# stm32f4discovery-daugherboard-v1-THT.net
KiCad netlist of a schematic drawn in EAGLE
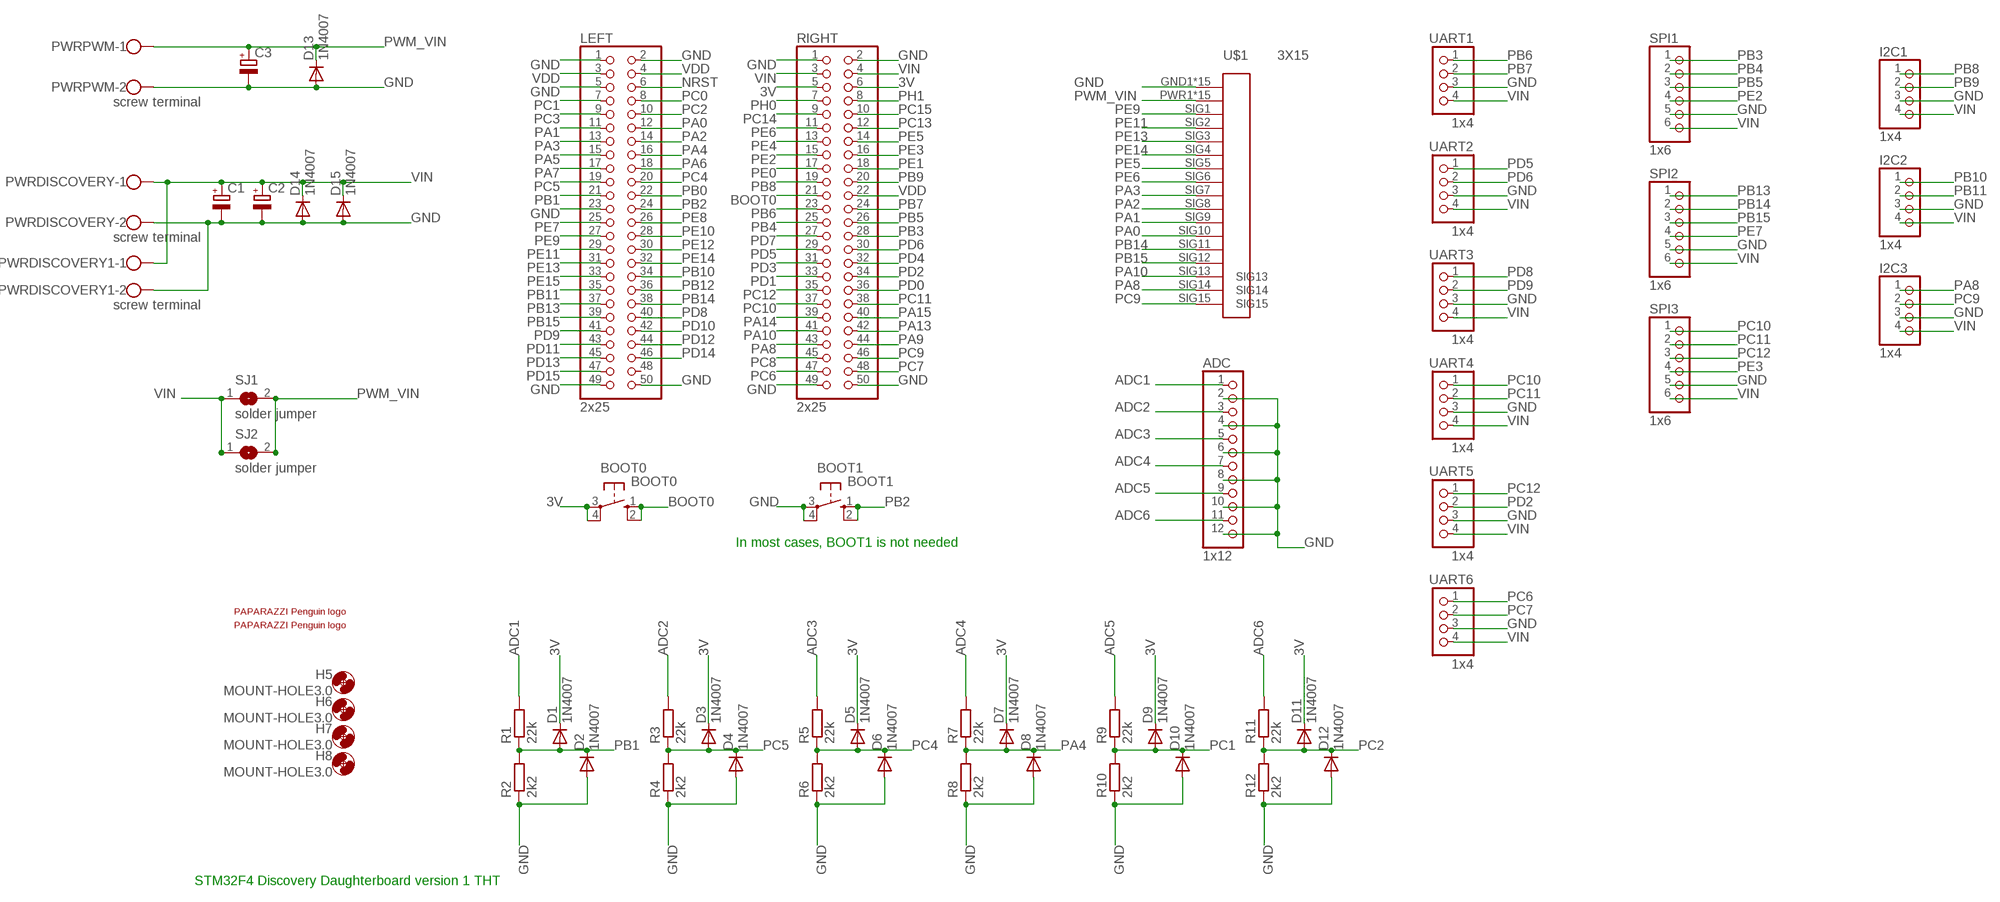
[diagram p0: schematic, sheet 1]

(export (version "E")
  (design (tool "Eeschema 10.0.6"))
  (components
    (comp (ref "ADC")
      (value "1x12")
      (footprint "eagle-import:1X12_90")
      (libsource (lib "eagle-import") (part "PINHD-1X12/90"))
    )
    (comp (ref "BOOT0")
      (value "BOOT0")
      (footprint "eagle-import:B3F-10XX")
      (fields (field (name "MPN") "B3F-1000"))
      (libsource (lib "eagle-import") (part "10-XX"))
    )
    (comp (ref "BOOT1")
      (value "BOOT1")
      (footprint "eagle-import:B3F-10XX")
      (fields (field (name "MPN") "B3F-1000"))
      (libsource (lib "eagle-import") (part "10-XX"))
    )
    (comp (ref "C1")
      (value "CPOL-EUE5-8.5")
      (footprint "eagle-import:E5-8,5")
      (libsource (lib "eagle-import") (part "CPOL-EUE5-8.5"))
    )
    (comp (ref "C2")
      (value "CPOL-EUE5-8.5")
      (footprint "eagle-import:E5-8,5")
      (libsource (lib "eagle-import") (part "CPOL-EUE5-8.5"))
    )
    (comp (ref "C3")
      (value "CPOL-EUE5-8.5")
      (footprint "eagle-import:E5-8,5")
      (libsource (lib "eagle-import") (part "CPOL-EUE5-8.5"))
    )
    (comp (ref "D1")
      (value "1N4007")
      (footprint "eagle-import:DO41-7.6_2")
      (libsource (lib "eagle-import") (part "1N4007"))
    )
    (comp (ref "D2")
      (value "1N4007")
      (footprint "eagle-import:DO41-7.6_2")
      (libsource (lib "eagle-import") (part "1N4007"))
    )
    (comp (ref "D3")
      (value "1N4007")
      (footprint "eagle-import:DO41-7.6_2")
      (libsource (lib "eagle-import") (part "1N4007"))
    )
    (comp (ref "D4")
      (value "1N4007")
      (footprint "eagle-import:DO41-7.6_2")
      (libsource (lib "eagle-import") (part "1N4007"))
    )
    (comp (ref "D5")
      (value "1N4007")
      (footprint "eagle-import:DO41-7.6_2")
      (libsource (lib "eagle-import") (part "1N4007"))
    )
    (comp (ref "D6")
      (value "1N4007")
      (footprint "eagle-import:DO41-7.6_2")
      (libsource (lib "eagle-import") (part "1N4007"))
    )
    (comp (ref "D7")
      (value "1N4007")
      (footprint "eagle-import:DO41-7.6_2")
      (libsource (lib "eagle-import") (part "1N4007"))
    )
    (comp (ref "D8")
      (value "1N4007")
      (footprint "eagle-import:DO41-7.6_2")
      (libsource (lib "eagle-import") (part "1N4007"))
    )
    (comp (ref "D9")
      (value "1N4007")
      (footprint "eagle-import:DO41-7.6_2")
      (libsource (lib "eagle-import") (part "1N4007"))
    )
    (comp (ref "D10")
      (value "1N4007")
      (footprint "eagle-import:DO41-7.6_2")
      (libsource (lib "eagle-import") (part "1N4007"))
    )
    (comp (ref "D11")
      (value "1N4007")
      (footprint "eagle-import:DO41-7.6_2")
      (libsource (lib "eagle-import") (part "1N4007"))
    )
    (comp (ref "D12")
      (value "1N4007")
      (footprint "eagle-import:DO41-7.6_2")
      (libsource (lib "eagle-import") (part "1N4007"))
    )
    (comp (ref "D13")
      (value "1N4007")
      (footprint "eagle-import:DO41-7.6_2")
      (libsource (lib "eagle-import") (part "1N4007"))
    )
    (comp (ref "D14")
      (value "1N4007")
      (footprint "eagle-import:DO41-7.6_2")
      (libsource (lib "eagle-import") (part "1N4007"))
    )
    (comp (ref "D15")
      (value "1N4007")
      (footprint "eagle-import:DO41-7.6_2")
      (libsource (lib "eagle-import") (part "1N4007"))
    )
    (comp (ref "H5")
      (value "MOUNT-HOLE3.0")
      (footprint "eagle-import:3,0")
      (libsource (lib "eagle-import") (part "MOUNT-HOLE3.0"))
    )
    (comp (ref "H6")
      (value "MOUNT-HOLE3.0")
      (footprint "eagle-import:3,0")
      (libsource (lib "eagle-import") (part "MOUNT-HOLE3.0"))
    )
    (comp (ref "H7")
      (value "MOUNT-HOLE3.0")
      (footprint "eagle-import:3,0")
      (libsource (lib "eagle-import") (part "MOUNT-HOLE3.0"))
    )
    (comp (ref "H8")
      (value "MOUNT-HOLE3.0")
      (footprint "eagle-import:3,0")
      (libsource (lib "eagle-import") (part "MOUNT-HOLE3.0"))
    )
    (comp (ref "I2C1")
      (value "1x4")
      (footprint "eagle-import:1X04_90")
      (libsource (lib "eagle-import") (part "PINHD-1X4/90"))
    )
    (comp (ref "I2C2")
      (value "1x4")
      (footprint "eagle-import:1X04_90")
      (libsource (lib "eagle-import") (part "PINHD-1X4/90"))
    )
    (comp (ref "I2C3")
      (value "1x4")
      (footprint "eagle-import:1X04_90")
      (libsource (lib "eagle-import") (part "PINHD-1X4/90"))
    )
    (comp (ref "LEFT")
      (value "2x25")
      (footprint "eagle-import:2X25")
      (libsource (lib "eagle-import") (part "PINHD-2X25"))
    )
    (comp (ref "PWRDISCOVERY")
      (value "screw terminal")
      (footprint "eagle-import:W237-102")
      (fields (field (name "MPN") "237-102"))
      (libsource (lib "eagle-import") (part "W237-102"))
    )
    (comp (ref "PWRDISCOVERY1")
      (value "screw terminal")
      (footprint "eagle-import:W237-102")
      (fields
        (field (name "MPN") "237-102")
        (field (name "MPN_1") "237-102")
        (field (name "OC_FARNELL") "unknown")
        (field (name "OC_NEWARK") "70K9898")
      )
      (libsource (lib "eagle-import") (part "W237-102"))
    )
    (comp (ref "PWRPWM")
      (value "screw terminal")
      (footprint "eagle-import:W237-102")
      (fields (field (name "MPN") "237-102"))
      (libsource (lib "eagle-import") (part "W237-102"))
    )
    (comp (ref "R1")
      (value "22k")
      (footprint "eagle-import:0204_7")
      (libsource (lib "eagle-import") (part "R-EU_0204/7"))
    )
    (comp (ref "R2")
      (value "2k2")
      (footprint "eagle-import:0204_7")
      (libsource (lib "eagle-import") (part "R-EU_0204/7"))
    )
    (comp (ref "R3")
      (value "22k")
      (footprint "eagle-import:0204_7")
      (libsource (lib "eagle-import") (part "R-EU_0204/7"))
    )
    (comp (ref "R4")
      (value "2k2")
      (footprint "eagle-import:0204_7")
      (libsource (lib "eagle-import") (part "R-EU_0204/7"))
    )
    (comp (ref "R5")
      (value "22k")
      (footprint "eagle-import:0204_7")
      (libsource (lib "eagle-import") (part "R-EU_0204/7"))
    )
    (comp (ref "R6")
      (value "2k2")
      (footprint "eagle-import:0204_7")
      (libsource (lib "eagle-import") (part "R-EU_0204/7"))
    )
    (comp (ref "R7")
      (value "22k")
      (footprint "eagle-import:0204_7")
      (libsource (lib "eagle-import") (part "R-EU_0204/7"))
    )
    (comp (ref "R8")
      (value "2k2")
      (footprint "eagle-import:0204_7")
      (libsource (lib "eagle-import") (part "R-EU_0204/7"))
    )
    (comp (ref "R9")
      (value "22k")
      (footprint "eagle-import:0204_7")
      (libsource (lib "eagle-import") (part "R-EU_0204/7"))
    )
    (comp (ref "R10")
      (value "2k2")
      (footprint "eagle-import:0204_7")
      (libsource (lib "eagle-import") (part "R-EU_0204/7"))
    )
    (comp (ref "R11")
      (value "22k")
      (footprint "eagle-import:0204_7")
      (libsource (lib "eagle-import") (part "R-EU_0204/7"))
    )
    (comp (ref "R12")
      (value "2k2")
      (footprint "eagle-import:0204_7")
      (libsource (lib "eagle-import") (part "R-EU_0204/7"))
    )
    (comp (ref "RIGHT")
      (value "2x25")
      (footprint "eagle-import:2X25")
      (libsource (lib "eagle-import") (part "PINHD-2X25"))
    )
    (comp (ref "SJ1")
      (value "solder jumper")
      (footprint "eagle-import:SJW")
      (libsource (lib "eagle-import") (part "SJW"))
    )
    (comp (ref "SJ2")
      (value "solder jumper")
      (footprint "eagle-import:SJW")
      (libsource (lib "eagle-import") (part "SJW"))
    )
    (comp (ref "SPI1")
      (value "1x6")
      (footprint "eagle-import:1X06_90")
      (libsource (lib "eagle-import") (part "PINHD-1X6/90"))
    )
    (comp (ref "SPI2")
      (value "1x6")
      (footprint "eagle-import:1X06_90")
      (libsource (lib "eagle-import") (part "PINHD-1X6/90"))
    )
    (comp (ref "SPI3")
      (value "1x6")
      (footprint "eagle-import:1X06_90")
      (libsource (lib "eagle-import") (part "PINHD-1X6/90"))
    )
    (comp (ref "U$1")
      (value "3X15")
      (footprint "eagle-import:3X15")
      (libsource (lib "eagle-import") (part "3X15"))
    )
    (comp (ref "U$2")
      (value "PAPARAZZI")
      (footprint "eagle-import:PAPARAZZI")
      (libsource (lib "eagle-import") (part "PAPARAZZI"))
    )
    (comp (ref "U$4")
      (value "üAüARAZZI_1400")
      (footprint "eagle-import:PAPARAZZI_1400")
      (libsource (lib "eagle-import") (part "üAüARAZZI_1400"))
    )
    (comp (ref "UART1")
      (value "1x4")
      (footprint "eagle-import:1X04_90")
      (libsource (lib "eagle-import") (part "PINHD-1X4/90"))
    )
    (comp (ref "UART2")
      (value "1x4")
      (footprint "eagle-import:1X04_90")
      (libsource (lib "eagle-import") (part "PINHD-1X4/90"))
    )
    (comp (ref "UART3")
      (value "1x4")
      (footprint "eagle-import:1X04_90")
      (libsource (lib "eagle-import") (part "PINHD-1X4/90"))
    )
    (comp (ref "UART4")
      (value "1x4")
      (footprint "eagle-import:1X04_90")
      (libsource (lib "eagle-import") (part "PINHD-1X4/90"))
    )
    (comp (ref "UART5")
      (value "1x4")
      (footprint "eagle-import:1X04_90")
      (libsource (lib "eagle-import") (part "PINHD-1X4/90"))
    )
    (comp (ref "UART6")
      (value "1x4")
      (footprint "eagle-import:1X04_90")
      (libsource (lib "eagle-import") (part "PINHD-1X4/90"))
    )
  )
  (nets
    (net (code "1") (name "/3V") (class "Default")
      (node (ref "BOOT0") (pin "3") (pinfunction "P_3") (pintype "passive"))
      (node (ref "BOOT0") (pin "4") (pinfunction "P1_4") (pintype "passive"))
      (node (ref "D1") (pin "C") (pinfunction "C_C") (pintype "passive"))
      (node (ref "D11") (pin "C") (pinfunction "C_C") (pintype "passive"))
      (node (ref "D3") (pin "C") (pinfunction "C_C") (pintype "passive"))
      (node (ref "D5") (pin "C") (pinfunction "C_C") (pintype "passive"))
      (node (ref "D7") (pin "C") (pinfunction "C_C") (pintype "passive"))
      (node (ref "D9") (pin "C") (pinfunction "C_C") (pintype "passive"))
      (node (ref "RIGHT") (pin "5") (pinfunction "5_5") (pintype "passive"))
      (node (ref "RIGHT") (pin "6") (pinfunction "6_6") (pintype "passive"))
    )
    (net (code "2") (name "/ADC1") (class "Default")
      (node (ref "ADC") (pin "1") (pinfunction "1_1") (pintype "passive"))
      (node (ref "R1") (pin "2") (pinfunction "2_2") (pintype "passive"))
    )
    (net (code "3") (name "/ADC2") (class "Default")
      (node (ref "ADC") (pin "3") (pinfunction "3_3") (pintype "passive"))
      (node (ref "R3") (pin "2") (pinfunction "2_2") (pintype "passive"))
    )
    (net (code "4") (name "/ADC3") (class "Default")
      (node (ref "ADC") (pin "5") (pinfunction "5_5") (pintype "passive"))
      (node (ref "R5") (pin "2") (pinfunction "2_2") (pintype "passive"))
    )
    (net (code "5") (name "/ADC4") (class "Default")
      (node (ref "ADC") (pin "7") (pinfunction "7_7") (pintype "passive"))
      (node (ref "R7") (pin "2") (pinfunction "2_2") (pintype "passive"))
    )
    (net (code "6") (name "/ADC5") (class "Default")
      (node (ref "ADC") (pin "9") (pinfunction "9_9") (pintype "passive"))
      (node (ref "R9") (pin "2") (pinfunction "2_2") (pintype "passive"))
    )
    (net (code "7") (name "/ADC6") (class "Default")
      (node (ref "ADC") (pin "11") (pinfunction "11_11") (pintype "passive"))
      (node (ref "R11") (pin "2") (pinfunction "2_2") (pintype "passive"))
    )
    (net (code "8") (name "/BOOT0") (class "Default")
      (node (ref "BOOT0") (pin "1") (pinfunction "S_1") (pintype "passive"))
      (node (ref "BOOT0") (pin "2") (pinfunction "S1_2") (pintype "passive"))
      (node (ref "RIGHT") (pin "21") (pinfunction "21_21") (pintype "passive"))
    )
    (net (code "9") (name "/GND") (class "Default")
      (node (ref "ADC") (pin "10") (pinfunction "10_10") (pintype "passive"))
      (node (ref "ADC") (pin "12") (pinfunction "12_12") (pintype "passive"))
      (node (ref "ADC") (pin "2") (pinfunction "2_2") (pintype "passive"))
      (node (ref "ADC") (pin "4") (pinfunction "4_4") (pintype "passive"))
      (node (ref "ADC") (pin "6") (pinfunction "6_6") (pintype "passive"))
      (node (ref "ADC") (pin "8") (pinfunction "8_8") (pintype "passive"))
      (node (ref "BOOT1") (pin "3") (pinfunction "P_3") (pintype "passive"))
      (node (ref "BOOT1") (pin "4") (pinfunction "P1_4") (pintype "passive"))
      (node (ref "C1") (pin "-") (pinfunction "-_-") (pintype "passive"))
      (node (ref "C2") (pin "-") (pinfunction "-_-") (pintype "passive"))
      (node (ref "C3") (pin "-") (pinfunction "-_-") (pintype "passive"))
      (node (ref "D10") (pin "A") (pinfunction "A_A") (pintype "passive"))
      (node (ref "D12") (pin "A") (pinfunction "A_A") (pintype "passive"))
      (node (ref "D13") (pin "A") (pinfunction "A_A") (pintype "passive"))
      (node (ref "D14") (pin "A") (pinfunction "A_A") (pintype "passive"))
      (node (ref "D15") (pin "A") (pinfunction "A_A") (pintype "passive"))
      (node (ref "D2") (pin "A") (pinfunction "A_A") (pintype "passive"))
      (node (ref "D4") (pin "A") (pinfunction "A_A") (pintype "passive"))
      (node (ref "D6") (pin "A") (pinfunction "A_A") (pintype "passive"))
      (node (ref "D8") (pin "A") (pinfunction "A_A") (pintype "passive"))
      (node (ref "I2C1") (pin "3") (pinfunction "3_3") (pintype "passive"))
      (node (ref "I2C2") (pin "3") (pinfunction "3_3") (pintype "passive"))
      (node (ref "I2C3") (pin "3") (pinfunction "3_3") (pintype "passive"))
      (node (ref "LEFT") (pin "1") (pinfunction "1_1") (pintype "passive"))
      (node (ref "LEFT") (pin "2") (pinfunction "2_2") (pintype "passive"))
      (node (ref "LEFT") (pin "23") (pinfunction "23_23") (pintype "passive"))
      (node (ref "LEFT") (pin "49") (pinfunction "49_49") (pintype "passive"))
      (node (ref "LEFT") (pin "5") (pinfunction "5_5") (pintype "passive"))
      (node (ref "LEFT") (pin "50") (pinfunction "50_50") (pintype "passive"))
      (node (ref "PWRDISCOVERY") (pin "2") (pinfunction "KL_2") (pintype "passive"))
      (node (ref "PWRDISCOVERY1") (pin "2") (pinfunction "KL_2") (pintype "passive"))
      (node (ref "PWRPWM") (pin "2") (pinfunction "KL_2") (pintype "passive"))
      (node (ref "R10") (pin "1") (pinfunction "1_1") (pintype "passive"))
      (node (ref "R12") (pin "1") (pinfunction "1_1") (pintype "passive"))
      (node (ref "R2") (pin "1") (pinfunction "1_1") (pintype "passive"))
      (node (ref "R4") (pin "1") (pinfunction "1_1") (pintype "passive"))
      (node (ref "R6") (pin "1") (pinfunction "1_1") (pintype "passive"))
      (node (ref "R8") (pin "1") (pinfunction "1_1") (pintype "passive"))
      (node (ref "RIGHT") (pin "1") (pinfunction "1_1") (pintype "passive"))
      (node (ref "RIGHT") (pin "2") (pinfunction "2_2") (pintype "passive"))
      (node (ref "RIGHT") (pin "49") (pinfunction "49_49") (pintype "passive"))
      (node (ref "RIGHT") (pin "50") (pinfunction "50_50") (pintype "passive"))
      (node (ref "SPI1") (pin "5") (pinfunction "5_5") (pintype "passive"))
      (node (ref "SPI2") (pin "5") (pinfunction "5_5") (pintype "passive"))
      (node (ref "SPI3") (pin "5") (pinfunction "5_5") (pintype "passive"))
      (node (ref "U$1") (pin "GND1") (pinfunction "GND_GND1") (pintype "bidirectional"))
      (node (ref "U$1") (pin "GND10") (pinfunction "GND_GND10") (pintype "bidirectional"))
      (node (ref "U$1") (pin "GND11") (pinfunction "GND_GND11") (pintype "bidirectional"))
      (node (ref "U$1") (pin "GND12") (pinfunction "GND_GND12") (pintype "bidirectional"))
      (node (ref "U$1") (pin "GND13") (pinfunction "GND_GND13") (pintype "bidirectional"))
      (node (ref "U$1") (pin "GND14") (pinfunction "GND_GND14") (pintype "bidirectional"))
      (node (ref "U$1") (pin "GND15") (pinfunction "GND_GND15") (pintype "bidirectional"))
      (node (ref "U$1") (pin "GND2") (pinfunction "GND_GND2") (pintype "bidirectional"))
      (node (ref "U$1") (pin "GND3") (pinfunction "GND_GND3") (pintype "bidirectional"))
      (node (ref "U$1") (pin "GND4") (pinfunction "GND_GND4") (pintype "bidirectional"))
      (node (ref "U$1") (pin "GND5") (pinfunction "GND_GND5") (pintype "bidirectional"))
      (node (ref "U$1") (pin "GND6") (pinfunction "GND_GND6") (pintype "bidirectional"))
      (node (ref "U$1") (pin "GND7") (pinfunction "GND_GND7") (pintype "bidirectional"))
      (node (ref "U$1") (pin "GND8") (pinfunction "GND_GND8") (pintype "bidirectional"))
      (node (ref "U$1") (pin "GND9") (pinfunction "GND_GND9") (pintype "bidirectional"))
      (node (ref "UART1") (pin "3") (pinfunction "3_3") (pintype "passive"))
      (node (ref "UART2") (pin "3") (pinfunction "3_3") (pintype "passive"))
      (node (ref "UART3") (pin "3") (pinfunction "3_3") (pintype "passive"))
      (node (ref "UART4") (pin "3") (pinfunction "3_3") (pintype "passive"))
      (node (ref "UART5") (pin "3") (pinfunction "3_3") (pintype "passive"))
      (node (ref "UART6") (pin "3") (pinfunction "3_3") (pintype "passive"))
    )
    (net (code "10") (name "/NRST") (class "Default")
      (node (ref "LEFT") (pin "6") (pinfunction "6_6") (pintype "passive"))
    )
    (net (code "11") (name "/PA0") (class "Default")
      (node (ref "LEFT") (pin "12") (pinfunction "12_12") (pintype "passive"))
      (node (ref "U$1") (pin "SIG10") (pinfunction "SIG10_SIG10") (pintype "bidirectional"))
    )
    (net (code "12") (name "/PA1") (class "Default")
      (node (ref "LEFT") (pin "11") (pinfunction "11_11") (pintype "passive"))
      (node (ref "U$1") (pin "SIG9") (pinfunction "SIG9_SIG9") (pintype "bidirectional"))
    )
    (net (code "13") (name "/PA2") (class "Default")
      (node (ref "LEFT") (pin "14") (pinfunction "14_14") (pintype "passive"))
      (node (ref "U$1") (pin "SIG8") (pinfunction "SIG8_SIG8") (pintype "bidirectional"))
    )
    (net (code "14") (name "/PA3") (class "Default")
      (node (ref "LEFT") (pin "13") (pinfunction "13_13") (pintype "passive"))
      (node (ref "U$1") (pin "SIG7") (pinfunction "SIG7_SIG7") (pintype "bidirectional"))
    )
    (net (code "15") (name "/PA4") (class "Default")
      (node (ref "D7") (pin "A") (pinfunction "A_A") (pintype "passive"))
      (node (ref "D8") (pin "C") (pinfunction "C_C") (pintype "passive"))
      (node (ref "LEFT") (pin "16") (pinfunction "16_16") (pintype "passive"))
      (node (ref "R7") (pin "1") (pinfunction "1_1") (pintype "passive"))
      (node (ref "R8") (pin "2") (pinfunction "2_2") (pintype "passive"))
    )
    (net (code "16") (name "/PA5") (class "Default")
      (node (ref "LEFT") (pin "15") (pinfunction "15_15") (pintype "passive"))
    )
    (net (code "17") (name "/PA6") (class "Default")
      (node (ref "LEFT") (pin "18") (pinfunction "18_18") (pintype "passive"))
    )
    (net (code "18") (name "/PA7") (class "Default")
      (node (ref "LEFT") (pin "17") (pinfunction "17_17") (pintype "passive"))
    )
    (net (code "19") (name "/PA8") (class "Default")
      (node (ref "I2C3") (pin "1") (pinfunction "1_1") (pintype "passive"))
      (node (ref "RIGHT") (pin "43") (pinfunction "43_43") (pintype "passive"))
      (node (ref "U$1") (pin "SIG14") (pinfunction "SIG14_SIG14") (pintype "bidirectional"))
    )
    (net (code "20") (name "/PA9") (class "Default")
      (node (ref "RIGHT") (pin "44") (pinfunction "44_44") (pintype "passive"))
    )
    (net (code "21") (name "/PA10") (class "Default")
      (node (ref "RIGHT") (pin "41") (pinfunction "41_41") (pintype "passive"))
      (node (ref "U$1") (pin "SIG13") (pinfunction "SIG13_SIG13") (pintype "bidirectional"))
    )
    (net (code "22") (name "/PA13") (class "Default")
      (node (ref "RIGHT") (pin "42") (pinfunction "42_42") (pintype "passive"))
    )
    (net (code "23") (name "/PA14") (class "Default")
      (node (ref "RIGHT") (pin "39") (pinfunction "39_39") (pintype "passive"))
    )
    (net (code "24") (name "/PA15") (class "Default")
      (node (ref "RIGHT") (pin "40") (pinfunction "40_40") (pintype "passive"))
    )
    (net (code "25") (name "/PB0") (class "Default")
      (node (ref "LEFT") (pin "22") (pinfunction "22_22") (pintype "passive"))
    )
    (net (code "26") (name "/PB1") (class "Default")
      (node (ref "D1") (pin "A") (pinfunction "A_A") (pintype "passive"))
      (node (ref "D2") (pin "C") (pinfunction "C_C") (pintype "passive"))
      (node (ref "LEFT") (pin "21") (pinfunction "21_21") (pintype "passive"))
      (node (ref "R1") (pin "1") (pinfunction "1_1") (pintype "passive"))
      (node (ref "R2") (pin "2") (pinfunction "2_2") (pintype "passive"))
    )
    (net (code "27") (name "/PB2") (class "Default")
      (node (ref "BOOT1") (pin "1") (pinfunction "S_1") (pintype "passive"))
      (node (ref "BOOT1") (pin "2") (pinfunction "S1_2") (pintype "passive"))
      (node (ref "LEFT") (pin "24") (pinfunction "24_24") (pintype "passive"))
    )
    (net (code "28") (name "/PB3") (class "Default")
      (node (ref "RIGHT") (pin "28") (pinfunction "28_28") (pintype "passive"))
      (node (ref "SPI1") (pin "1") (pinfunction "1_1") (pintype "passive"))
    )
    (net (code "29") (name "/PB4") (class "Default")
      (node (ref "RIGHT") (pin "25") (pinfunction "25_25") (pintype "passive"))
      (node (ref "SPI1") (pin "2") (pinfunction "2_2") (pintype "passive"))
    )
    (net (code "30") (name "/PB5") (class "Default")
      (node (ref "RIGHT") (pin "26") (pinfunction "26_26") (pintype "passive"))
      (node (ref "SPI1") (pin "3") (pinfunction "3_3") (pintype "passive"))
    )
    (net (code "31") (name "/PB6") (class "Default")
      (node (ref "RIGHT") (pin "23") (pinfunction "23_23") (pintype "passive"))
      (node (ref "UART1") (pin "1") (pinfunction "1_1") (pintype "passive"))
    )
    (net (code "32") (name "/PB7") (class "Default")
      (node (ref "RIGHT") (pin "24") (pinfunction "24_24") (pintype "passive"))
      (node (ref "UART1") (pin "2") (pinfunction "2_2") (pintype "passive"))
    )
    (net (code "33") (name "/PB8") (class "Default")
      (node (ref "I2C1") (pin "1") (pinfunction "1_1") (pintype "passive"))
      (node (ref "RIGHT") (pin "19") (pinfunction "19_19") (pintype "passive"))
    )
    (net (code "34") (name "/PB9") (class "Default")
      (node (ref "I2C1") (pin "2") (pinfunction "2_2") (pintype "passive"))
      (node (ref "RIGHT") (pin "20") (pinfunction "20_20") (pintype "passive"))
    )
    (net (code "35") (name "/PB10") (class "Default")
      (node (ref "I2C2") (pin "1") (pinfunction "1_1") (pintype "passive"))
      (node (ref "LEFT") (pin "34") (pinfunction "34_34") (pintype "passive"))
    )
    (net (code "36") (name "/PB11") (class "Default")
      (node (ref "I2C2") (pin "2") (pinfunction "2_2") (pintype "passive"))
      (node (ref "LEFT") (pin "35") (pinfunction "35_35") (pintype "passive"))
    )
    (net (code "37") (name "/PB12") (class "Default")
      (node (ref "LEFT") (pin "36") (pinfunction "36_36") (pintype "passive"))
    )
    (net (code "38") (name "/PB13") (class "Default")
      (node (ref "LEFT") (pin "37") (pinfunction "37_37") (pintype "passive"))
      (node (ref "SPI2") (pin "1") (pinfunction "1_1") (pintype "passive"))
    )
    (net (code "39") (name "/PB14") (class "Default")
      (node (ref "LEFT") (pin "38") (pinfunction "38_38") (pintype "passive"))
      (node (ref "SPI2") (pin "2") (pinfunction "2_2") (pintype "passive"))
      (node (ref "U$1") (pin "SIG11") (pinfunction "SIG11_SIG11") (pintype "bidirectional"))
    )
    (net (code "40") (name "/PB15") (class "Default")
      (node (ref "LEFT") (pin "39") (pinfunction "39_39") (pintype "passive"))
      (node (ref "SPI2") (pin "3") (pinfunction "3_3") (pintype "passive"))
      (node (ref "U$1") (pin "SIG12") (pinfunction "SIG12_SIG12") (pintype "bidirectional"))
    )
    (net (code "41") (name "/PC0") (class "Default")
      (node (ref "LEFT") (pin "8") (pinfunction "8_8") (pintype "passive"))
    )
    (net (code "42") (name "/PC1") (class "Default")
      (node (ref "D10") (pin "C") (pinfunction "C_C") (pintype "passive"))
      (node (ref "D9") (pin "A") (pinfunction "A_A") (pintype "passive"))
      (node (ref "LEFT") (pin "7") (pinfunction "7_7") (pintype "passive"))
      (node (ref "R10") (pin "2") (pinfunction "2_2") (pintype "passive"))
      (node (ref "R9") (pin "1") (pinfunction "1_1") (pintype "passive"))
    )
    (net (code "43") (name "/PC2") (class "Default")
      (node (ref "D11") (pin "A") (pinfunction "A_A") (pintype "passive"))
      (node (ref "D12") (pin "C") (pinfunction "C_C") (pintype "passive"))
      (node (ref "LEFT") (pin "10") (pinfunction "10_10") (pintype "passive"))
      (node (ref "R11") (pin "1") (pinfunction "1_1") (pintype "passive"))
      (node (ref "R12") (pin "2") (pinfunction "2_2") (pintype "passive"))
    )
    (net (code "44") (name "/PC3") (class "Default")
      (node (ref "LEFT") (pin "9") (pinfunction "9_9") (pintype "passive"))
    )
    (net (code "45") (name "/PC4") (class "Default")
      (node (ref "D5") (pin "A") (pinfunction "A_A") (pintype "passive"))
      (node (ref "D6") (pin "C") (pinfunction "C_C") (pintype "passive"))
      (node (ref "LEFT") (pin "20") (pinfunction "20_20") (pintype "passive"))
      (node (ref "R5") (pin "1") (pinfunction "1_1") (pintype "passive"))
      (node (ref "R6") (pin "2") (pinfunction "2_2") (pintype "passive"))
    )
    (net (code "46") (name "/PC5") (class "Default")
      (node (ref "D3") (pin "A") (pinfunction "A_A") (pintype "passive"))
      (node (ref "D4") (pin "C") (pinfunction "C_C") (pintype "passive"))
      (node (ref "LEFT") (pin "19") (pinfunction "19_19") (pintype "passive"))
      (node (ref "R3") (pin "1") (pinfunction "1_1") (pintype "passive"))
      (node (ref "R4") (pin "2") (pinfunction "2_2") (pintype "passive"))
    )
    (net (code "47") (name "/PC6") (class "Default")
      (node (ref "RIGHT") (pin "47") (pinfunction "47_47") (pintype "passive"))
      (node (ref "UART6") (pin "1") (pinfunction "1_1") (pintype "passive"))
    )
    (net (code "48") (name "/PC7") (class "Default")
      (node (ref "RIGHT") (pin "48") (pinfunction "48_48") (pintype "passive"))
      (node (ref "UART6") (pin "2") (pinfunction "2_2") (pintype "passive"))
    )
    (net (code "49") (name "/PC8") (class "Default")
      (node (ref "RIGHT") (pin "45") (pinfunction "45_45") (pintype "passive"))
    )
    (net (code "50") (name "/PC9") (class "Default")
      (node (ref "I2C3") (pin "2") (pinfunction "2_2") (pintype "passive"))
      (node (ref "RIGHT") (pin "46") (pinfunction "46_46") (pintype "passive"))
      (node (ref "U$1") (pin "SIG15") (pinfunction "SIG15_SIG15") (pintype "bidirectional"))
    )
    (net (code "51") (name "/PC10") (class "Default")
      (node (ref "RIGHT") (pin "37") (pinfunction "37_37") (pintype "passive"))
      (node (ref "SPI3") (pin "1") (pinfunction "1_1") (pintype "passive"))
      (node (ref "UART4") (pin "1") (pinfunction "1_1") (pintype "passive"))
    )
    (net (code "52") (name "/PC11") (class "Default")
      (node (ref "RIGHT") (pin "38") (pinfunction "38_38") (pintype "passive"))
      (node (ref "SPI3") (pin "2") (pinfunction "2_2") (pintype "passive"))
      (node (ref "UART4") (pin "2") (pinfunction "2_2") (pintype "passive"))
    )
    (net (code "53") (name "/PC12") (class "Default")
      (node (ref "RIGHT") (pin "35") (pinfunction "35_35") (pintype "passive"))
      (node (ref "SPI3") (pin "3") (pinfunction "3_3") (pintype "passive"))
      (node (ref "UART5") (pin "1") (pinfunction "1_1") (pintype "passive"))
    )
    (net (code "54") (name "/PC13") (class "Default")
      (node (ref "RIGHT") (pin "12") (pinfunction "12_12") (pintype "passive"))
    )
    (net (code "55") (name "/PC14") (class "Default")
      (node (ref "RIGHT") (pin "9") (pinfunction "9_9") (pintype "passive"))
    )
    (net (code "56") (name "/PC15") (class "Default")
      (node (ref "RIGHT") (pin "10") (pinfunction "10_10") (pintype "passive"))
    )
    (net (code "57") (name "/PD0") (class "Default")
      (node (ref "RIGHT") (pin "36") (pinfunction "36_36") (pintype "passive"))
    )
    (net (code "58") (name "/PD1") (class "Default")
      (node (ref "RIGHT") (pin "33") (pinfunction "33_33") (pintype "passive"))
    )
    (net (code "59") (name "/PD2") (class "Default")
      (node (ref "RIGHT") (pin "34") (pinfunction "34_34") (pintype "passive"))
      (node (ref "UART5") (pin "2") (pinfunction "2_2") (pintype "passive"))
    )
    (net (code "60") (name "/PD3") (class "Default")
      (node (ref "RIGHT") (pin "31") (pinfunction "31_31") (pintype "passive"))
    )
    (net (code "61") (name "/PD4") (class "Default")
      (node (ref "RIGHT") (pin "32") (pinfunction "32_32") (pintype "passive"))
    )
    (net (code "62") (name "/PD5") (class "Default")
      (node (ref "RIGHT") (pin "29") (pinfunction "29_29") (pintype "passive"))
      (node (ref "UART2") (pin "1") (pinfunction "1_1") (pintype "passive"))
    )
    (net (code "63") (name "/PD6") (class "Default")
      (node (ref "RIGHT") (pin "30") (pinfunction "30_30") (pintype "passive"))
      (node (ref "UART2") (pin "2") (pinfunction "2_2") (pintype "passive"))
    )
    (net (code "64") (name "/PD7") (class "Default")
      (node (ref "RIGHT") (pin "27") (pinfunction "27_27") (pintype "passive"))
    )
    (net (code "65") (name "/PD8") (class "Default")
      (node (ref "LEFT") (pin "40") (pinfunction "40_40") (pintype "passive"))
      (node (ref "UART3") (pin "1") (pinfunction "1_1") (pintype "passive"))
    )
    (net (code "66") (name "/PD9") (class "Default")
      (node (ref "LEFT") (pin "41") (pinfunction "41_41") (pintype "passive"))
      (node (ref "UART3") (pin "2") (pinfunction "2_2") (pintype "passive"))
    )
    (net (code "67") (name "/PD10") (class "Default")
      (node (ref "LEFT") (pin "42") (pinfunction "42_42") (pintype "passive"))
    )
    (net (code "68") (name "/PD11") (class "Default")
      (node (ref "LEFT") (pin "43") (pinfunction "43_43") (pintype "passive"))
    )
    (net (code "69") (name "/PD12") (class "Default")
      (node (ref "LEFT") (pin "44") (pinfunction "44_44") (pintype "passive"))
    )
    (net (code "70") (name "/PD13") (class "Default")
      (node (ref "LEFT") (pin "45") (pinfunction "45_45") (pintype "passive"))
    )
    (net (code "71") (name "/PD14") (class "Default")
      (node (ref "LEFT") (pin "46") (pinfunction "46_46") (pintype "passive"))
    )
    (net (code "72") (name "/PD15") (class "Default")
      (node (ref "LEFT") (pin "47") (pinfunction "47_47") (pintype "passive"))
    )
    (net (code "73") (name "/PE0") (class "Default")
      (node (ref "RIGHT") (pin "17") (pinfunction "17_17") (pintype "passive"))
    )
    (net (code "74") (name "/PE1") (class "Default")
      (node (ref "RIGHT") (pin "18") (pinfunction "18_18") (pintype "passive"))
    )
    (net (code "75") (name "/PE2") (class "Default")
      (node (ref "RIGHT") (pin "15") (pinfunction "15_15") (pintype "passive"))
      (node (ref "SPI1") (pin "4") (pinfunction "4_4") (pintype "passive"))
    )
    (net (code "76") (name "/PE3") (class "Default")
      (node (ref "RIGHT") (pin "16") (pinfunction "16_16") (pintype "passive"))
      (node (ref "SPI3") (pin "4") (pinfunction "4_4") (pintype "passive"))
    )
    (net (code "77") (name "/PE4") (class "Default")
      (node (ref "RIGHT") (pin "13") (pinfunction "13_13") (pintype "passive"))
    )
    (net (code "78") (name "/PE5") (class "Default")
      (node (ref "RIGHT") (pin "14") (pinfunction "14_14") (pintype "passive"))
      (node (ref "U$1") (pin "SIG5") (pinfunction "SIG5_SIG5") (pintype "bidirectional"))
    )
    (net (code "79") (name "/PE6") (class "Default")
      (node (ref "RIGHT") (pin "11") (pinfunction "11_11") (pintype "passive"))
      (node (ref "U$1") (pin "SIG6") (pinfunction "SIG6_SIG6") (pintype "bidirectional"))
    )
    (net (code "80") (name "/PE7") (class "Default")
      (node (ref "LEFT") (pin "25") (pinfunction "25_25") (pintype "passive"))
      (node (ref "SPI2") (pin "4") (pinfunction "4_4") (pintype "passive"))
    )
    (net (code "81") (name "/PE8") (class "Default")
      (node (ref "LEFT") (pin "26") (pinfunction "26_26") (pintype "passive"))
    )
    (net (code "82") (name "/PE9") (class "Default")
      (node (ref "LEFT") (pin "27") (pinfunction "27_27") (pintype "passive"))
      (node (ref "U$1") (pin "SIG1") (pinfunction "SIG1_SIG1") (pintype "bidirectional"))
    )
    (net (code "83") (name "/PE10") (class "Default")
      (node (ref "LEFT") (pin "28") (pinfunction "28_28") (pintype "passive"))
    )
    (net (code "84") (name "/PE11") (class "Default")
      (node (ref "LEFT") (pin "29") (pinfunction "29_29") (pintype "passive"))
      (node (ref "U$1") (pin "SIG2") (pinfunction "SIG2_SIG2") (pintype "bidirectional"))
    )
    (net (code "85") (name "/PE12") (class "Default")
      (node (ref "LEFT") (pin "30") (pinfunction "30_30") (pintype "passive"))
    )
    (net (code "86") (name "/PE13") (class "Default")
      (node (ref "LEFT") (pin "31") (pinfunction "31_31") (pintype "passive"))
      (node (ref "U$1") (pin "SIG3") (pinfunction "SIG3_SIG3") (pintype "bidirectional"))
    )
    (net (code "87") (name "/PE14") (class "Default")
      (node (ref "LEFT") (pin "32") (pinfunction "32_32") (pintype "passive"))
      (node (ref "U$1") (pin "SIG4") (pinfunction "SIG4_SIG4") (pintype "bidirectional"))
    )
    (net (code "88") (name "/PE15") (class "Default")
      (node (ref "LEFT") (pin "33") (pinfunction "33_33") (pintype "passive"))
    )
    (net (code "89") (name "/PH0") (class "Default")
      (node (ref "RIGHT") (pin "7") (pinfunction "7_7") (pintype "passive"))
    )
    (net (code "90") (name "/PH1") (class "Default")
      (node (ref "RIGHT") (pin "8") (pinfunction "8_8") (pintype "passive"))
    )
    (net (code "91") (name "/PWM_VIN") (class "Default")
      (node (ref "C3") (pin "+") (pinfunction "+_+") (pintype "passive"))
      (node (ref "D13") (pin "C") (pinfunction "C_C") (pintype "passive"))
      (node (ref "PWRPWM") (pin "1") (pinfunction "KL_1") (pintype "passive"))
      (node (ref "SJ1") (pin "2") (pinfunction "2_2") (pintype "passive"))
      (node (ref "SJ2") (pin "2") (pinfunction "2_2") (pintype "passive"))
      (node (ref "U$1") (pin "PWR1") (pinfunction "PWR_PWR1") (pintype "bidirectional"))
      (node (ref "U$1") (pin "PWR10") (pinfunction "PWR_PWR10") (pintype "bidirectional"))
      (node (ref "U$1") (pin "PWR11") (pinfunction "PWR_PWR11") (pintype "bidirectional"))
      (node (ref "U$1") (pin "PWR12") (pinfunction "PWR_PWR12") (pintype "bidirectional"))
      (node (ref "U$1") (pin "PWR13") (pinfunction "PWR_PWR13") (pintype "bidirectional"))
      (node (ref "U$1") (pin "PWR14") (pinfunction "PWR_PWR14") (pintype "bidirectional"))
      (node (ref "U$1") (pin "PWR15") (pinfunction "PWR_PWR15") (pintype "bidirectional"))
      (node (ref "U$1") (pin "PWR2") (pinfunction "PWR_PWR2") (pintype "bidirectional"))
      (node (ref "U$1") (pin "PWR3") (pinfunction "PWR_PWR3") (pintype "bidirectional"))
      (node (ref "U$1") (pin "PWR4") (pinfunction "PWR_PWR4") (pintype "bidirectional"))
      (node (ref "U$1") (pin "PWR5") (pinfunction "PWR_PWR5") (pintype "bidirectional"))
      (node (ref "U$1") (pin "PWR6") (pinfunction "PWR_PWR6") (pintype "bidirectional"))
      (node (ref "U$1") (pin "PWR7") (pinfunction "PWR_PWR7") (pintype "bidirectional"))
      (node (ref "U$1") (pin "PWR8") (pinfunction "PWR_PWR8") (pintype "bidirectional"))
      (node (ref "U$1") (pin "PWR9") (pinfunction "PWR_PWR9") (pintype "bidirectional"))
    )
    (net (code "92") (name "/VDD") (class "Default")
      (node (ref "LEFT") (pin "3") (pinfunction "3_3") (pintype "passive"))
      (node (ref "LEFT") (pin "4") (pinfunction "4_4") (pintype "passive"))
      (node (ref "RIGHT") (pin "22") (pinfunction "22_22") (pintype "passive"))
    )
    (net (code "93") (name "/VIN") (class "Default")
      (node (ref "C1") (pin "+") (pinfunction "+_+") (pintype "passive"))
      (node (ref "C2") (pin "+") (pinfunction "+_+") (pintype "passive"))
      (node (ref "D14") (pin "C") (pinfunction "C_C") (pintype "passive"))
      (node (ref "D15") (pin "C") (pinfunction "C_C") (pintype "passive"))
      (node (ref "I2C1") (pin "4") (pinfunction "4_4") (pintype "passive"))
      (node (ref "I2C2") (pin "4") (pinfunction "4_4") (pintype "passive"))
      (node (ref "I2C3") (pin "4") (pinfunction "4_4") (pintype "passive"))
      (node (ref "PWRDISCOVERY") (pin "1") (pinfunction "KL_1") (pintype "passive"))
      (node (ref "PWRDISCOVERY1") (pin "1") (pinfunction "KL_1") (pintype "passive"))
      (node (ref "RIGHT") (pin "3") (pinfunction "3_3") (pintype "passive"))
      (node (ref "RIGHT") (pin "4") (pinfunction "4_4") (pintype "passive"))
      (node (ref "SJ1") (pin "1") (pinfunction "1_1") (pintype "passive"))
      (node (ref "SJ2") (pin "1") (pinfunction "1_1") (pintype "passive"))
      (node (ref "SPI1") (pin "6") (pinfunction "6_6") (pintype "passive"))
      (node (ref "SPI2") (pin "6") (pinfunction "6_6") (pintype "passive"))
      (node (ref "SPI3") (pin "6") (pinfunction "6_6") (pintype "passive"))
      (node (ref "UART1") (pin "4") (pinfunction "4_4") (pintype "passive"))
      (node (ref "UART2") (pin "4") (pinfunction "4_4") (pintype "passive"))
      (node (ref "UART3") (pin "4") (pinfunction "4_4") (pintype "passive"))
      (node (ref "UART4") (pin "4") (pinfunction "4_4") (pintype "passive"))
      (node (ref "UART5") (pin "4") (pinfunction "4_4") (pintype "passive"))
      (node (ref "UART6") (pin "4") (pinfunction "4_4") (pintype "passive"))
    )
    (net (code "94") (name "unconnected-(LEFT-Pad48)") (class "Default")
      (node (ref "LEFT") (pin "48") (pinfunction "48_48") (pintype "passive"))
    )
  )
)
